# ProPrj_Trumpet_2025-12-14.net
KiCad netlist of a schematic drawn in EasyEDA Pro
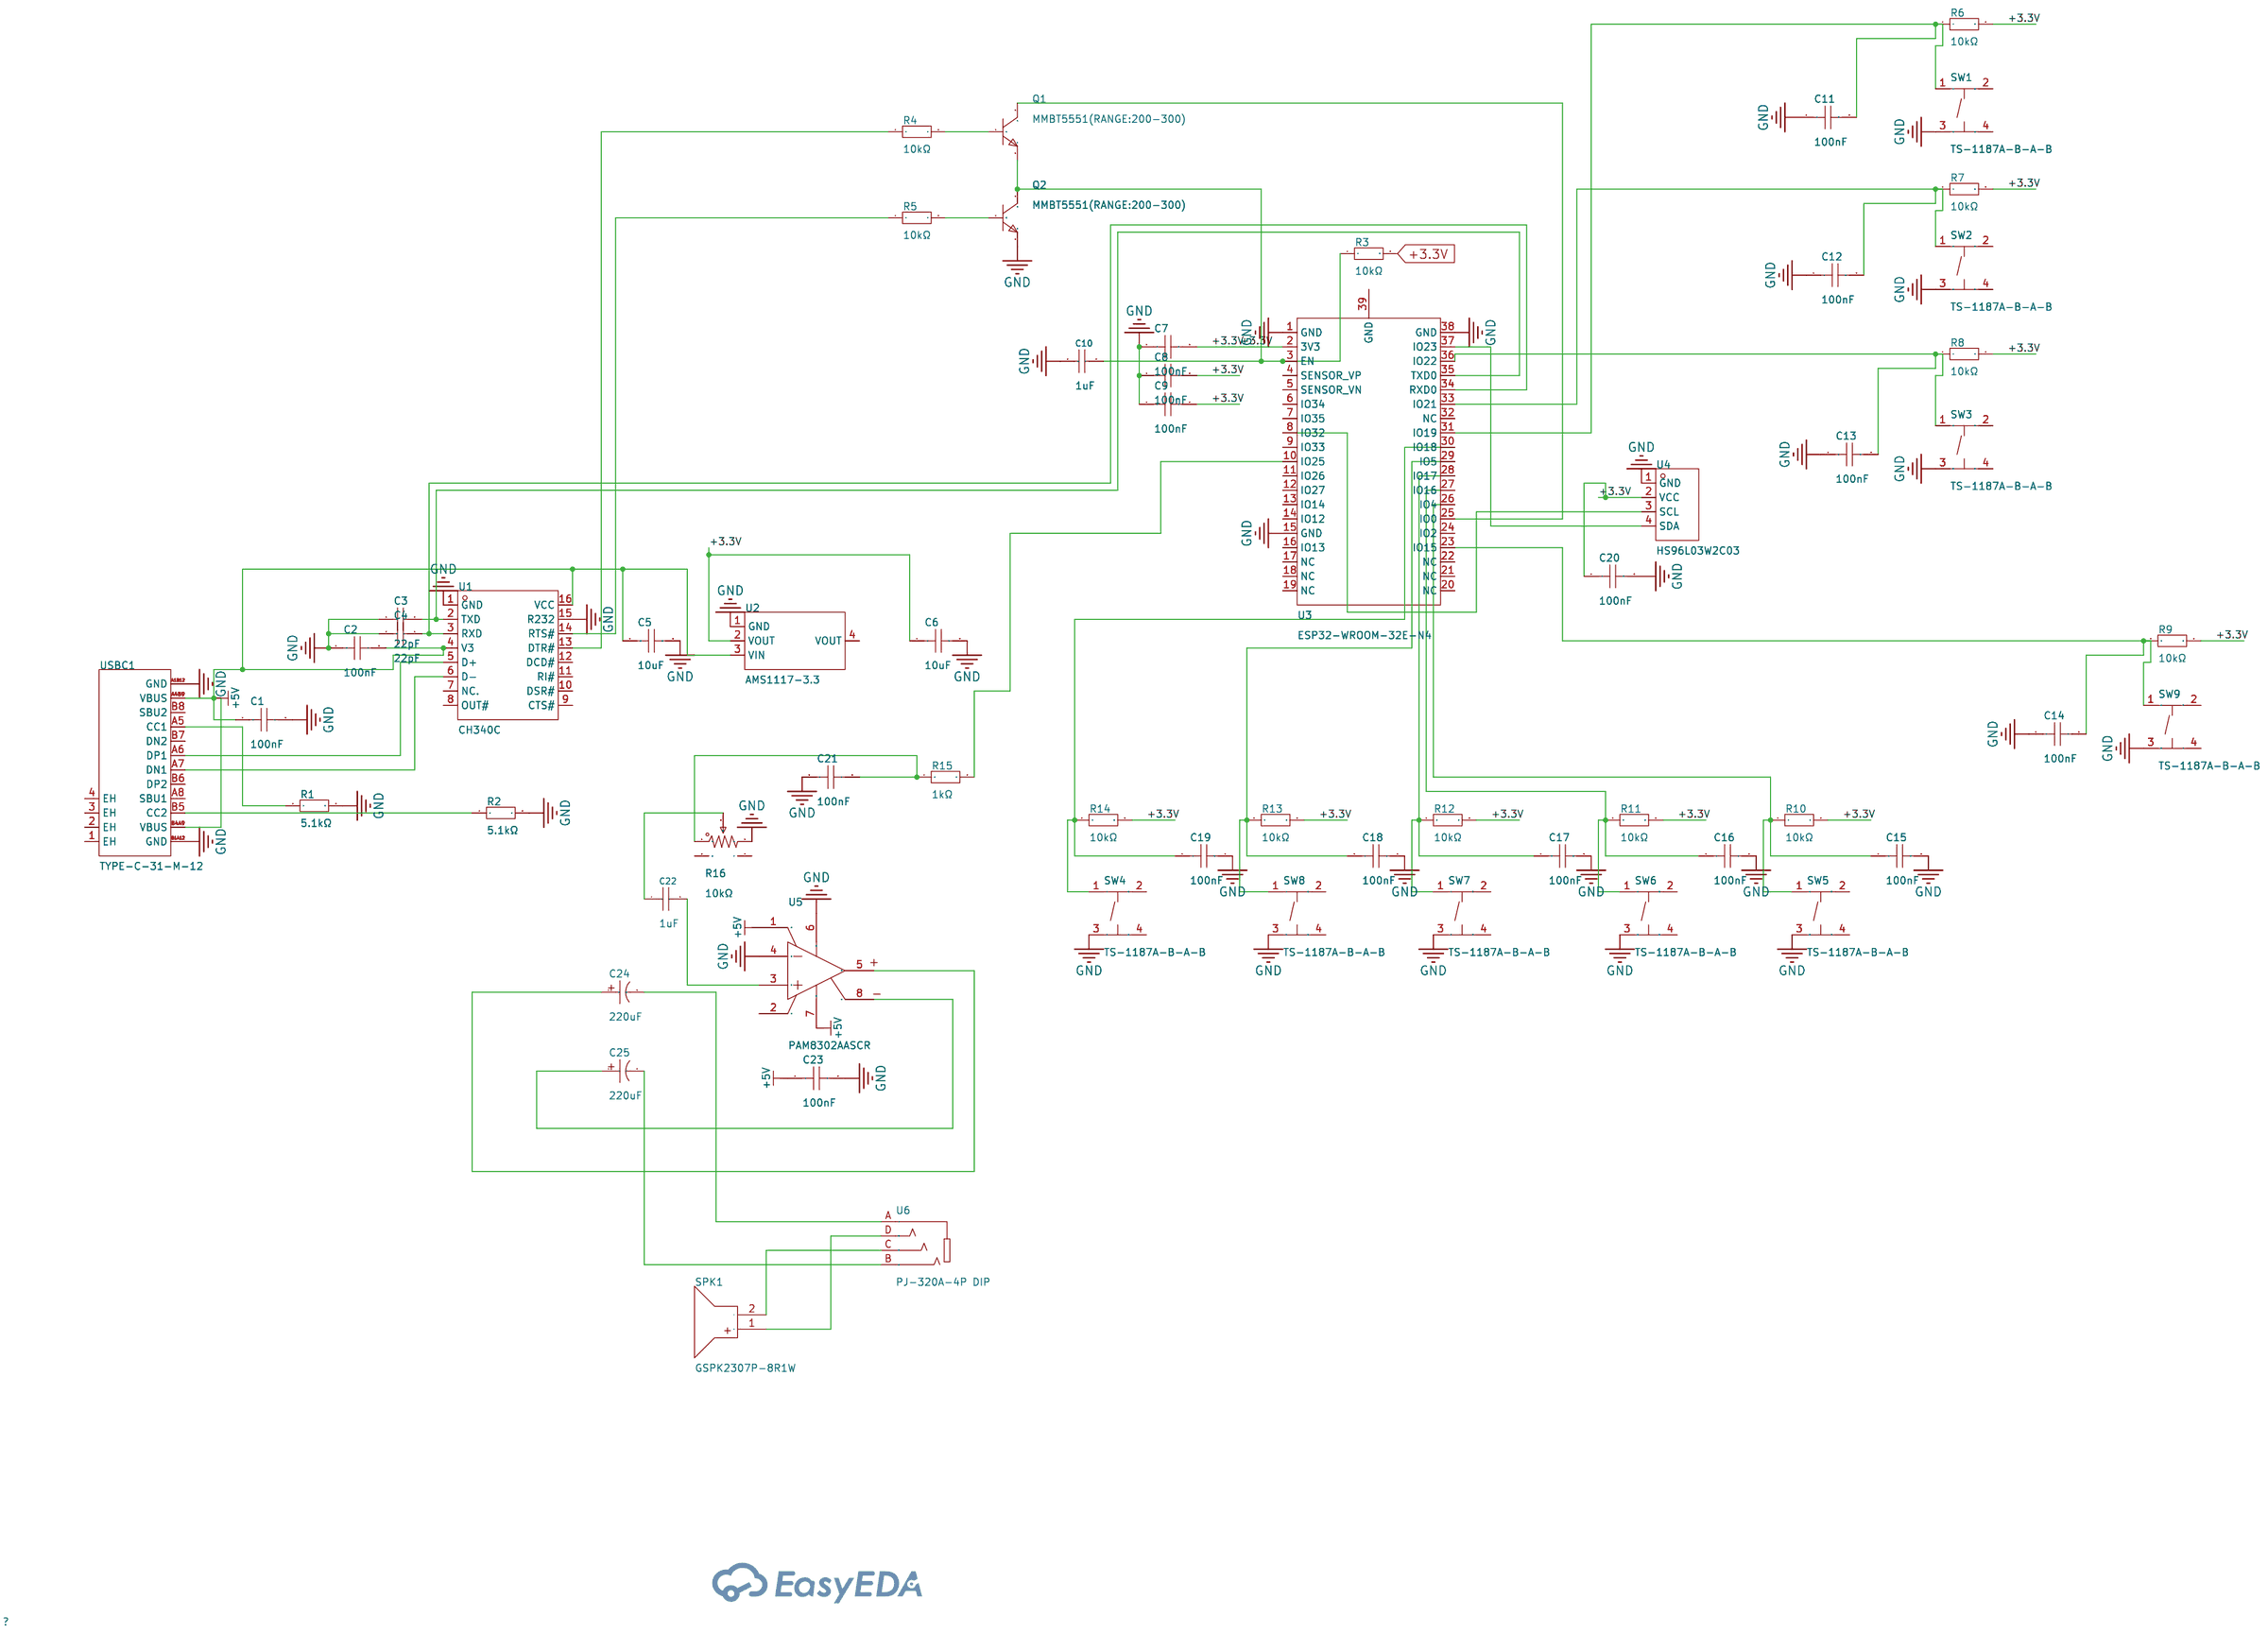
[diagram p0: schematic sheet]

(export (version "E")
  (design (tool "Eeschema 10.0.6"))
  (components
    (comp (ref "C1")
      (value "100nF")
      (footprint "easyedapro:C0805")
      (description "Capacitance:100nF Tolerance:±10% Tolerance:±10% Voltage Rating:50V Temperature Coefficient:X7R")
      (fields
        (field (name "Manufacturer Part") "CC0805KRX7R9BB104")
        (field (name "Manufacturer") "YAGEO(国巨)")
      )
      (libsource (lib "easyedapro") (part "CC0805KRX7R9BB104"))
    )
    (comp (ref "C2")
      (value "100nF")
      (footprint "easyedapro:C0805")
      (description "Capacitance:100nF Tolerance:±10% Tolerance:±10% Voltage Rating:50V Temperature Coefficient:X7R")
      (fields
        (field (name "Manufacturer Part") "CC0805KRX7R9BB104")
        (field (name "Manufacturer") "YAGEO(国巨)")
      )
      (libsource (lib "easyedapro") (part "CC0805KRX7R9BB104"))
    )
    (comp (ref "C3")
      (value "22pF")
      (footprint "easyedapro:C0402")
      (fields (field (name "Manufacturer Part") "0402CG220J500NT") (field (name "Manufacturer") "FH(风华)"))
      (libsource (lib "easyedapro") (part "0402CG220J500NT"))
    )
    (comp (ref "C4")
      (value "22pF")
      (footprint "easyedapro:C0402")
      (fields (field (name "Manufacturer Part") "0402CG220J500NT") (field (name "Manufacturer") "FH(风华)"))
      (libsource (lib "easyedapro") (part "0402CG220J500NT"))
    )
    (comp (ref "C5")
      (value "10uF")
      (footprint "easyedapro:C0805")
      (description "Capacitance:10uF Tolerance:±10% Tolerance:±10% Voltage Rating:25V Temperature Coefficient:X5R")
      (fields
        (field (name "Manufacturer Part") "CL21A106KAYNNNE")
        (field (name "Manufacturer") "SAMSUNG(三星)")
      )
      (libsource (lib "easyedapro") (part "CL21A106KAYNNNE"))
    )
    (comp (ref "C6")
      (value "10uF")
      (footprint "easyedapro:C0805")
      (description "Capacitance:10uF Tolerance:±10% Tolerance:±10% Voltage Rating:25V Temperature Coefficient:X5R")
      (fields
        (field (name "Manufacturer Part") "CL21A106KAYNNNE")
        (field (name "Manufacturer") "SAMSUNG(三星)")
      )
      (libsource (lib "easyedapro") (part "CL21A106KAYNNNE"))
    )
    (comp (ref "C7")
      (value "100nF")
      (footprint "easyedapro:C0805")
      (description "Capacitance:100nF Tolerance:±10% Tolerance:±10% Voltage Rating:50V Temperature Coefficient:X7R")
      (fields
        (field (name "Manufacturer Part") "CC0805KRX7R9BB104")
        (field (name "Manufacturer") "YAGEO(国巨)")
      )
      (libsource (lib "easyedapro") (part "CC0805KRX7R9BB104"))
    )
    (comp (ref "C8")
      (value "100nF")
      (footprint "easyedapro:C0805")
      (description "Capacitance:100nF Tolerance:±10% Tolerance:±10% Voltage Rating:50V Temperature Coefficient:X7R")
      (fields
        (field (name "Manufacturer Part") "CC0805KRX7R9BB104")
        (field (name "Manufacturer") "YAGEO(国巨)")
      )
      (libsource (lib "easyedapro") (part "CC0805KRX7R9BB104"))
    )
    (comp (ref "C9")
      (value "100nF")
      (footprint "easyedapro:C0805")
      (description "Capacitance:100nF Tolerance:±10% Tolerance:±10% Voltage Rating:50V Temperature Coefficient:X7R")
      (fields
        (field (name "Manufacturer Part") "CC0805KRX7R9BB104")
        (field (name "Manufacturer") "YAGEO(国巨)")
      )
      (libsource (lib "easyedapro") (part "CC0805KRX7R9BB104"))
    )
    (comp (ref "C10")
      (value "1uF")
      (footprint "easyedapro:C0805")
      (description "Capacitance:1uF Tolerance:±10% Tolerance:±10% Voltage Rating:50V Temperature Coefficient:X7R")
      (fields
        (field (name "Manufacturer Part") "CL21B105KBFNNNE")
        (field (name "Manufacturer") "SAMSUNG(三星)")
      )
      (libsource (lib "easyedapro") (part "CL21B105KBFNNNE"))
    )
    (comp (ref "C11")
      (value "100nF")
      (footprint "easyedapro:C0805")
      (description "Capacitance:100nF Tolerance:±10% Tolerance:±10% Voltage Rating:50V Temperature Coefficient:X7R")
      (fields
        (field (name "Manufacturer Part") "CC0805KRX7R9BB104")
        (field (name "Manufacturer") "YAGEO(国巨)")
      )
      (libsource (lib "easyedapro") (part "CC0805KRX7R9BB104"))
    )
    (comp (ref "C12")
      (value "100nF")
      (footprint "easyedapro:C0805")
      (description "Capacitance:100nF Tolerance:±10% Tolerance:±10% Voltage Rating:50V Temperature Coefficient:X7R")
      (fields
        (field (name "Manufacturer Part") "CC0805KRX7R9BB104")
        (field (name "Manufacturer") "YAGEO(国巨)")
      )
      (libsource (lib "easyedapro") (part "CC0805KRX7R9BB104"))
    )
    (comp (ref "C13")
      (value "100nF")
      (footprint "easyedapro:C0805")
      (description "Capacitance:100nF Tolerance:±10% Tolerance:±10% Voltage Rating:50V Temperature Coefficient:X7R")
      (fields
        (field (name "Manufacturer Part") "CC0805KRX7R9BB104")
        (field (name "Manufacturer") "YAGEO(国巨)")
      )
      (libsource (lib "easyedapro") (part "CC0805KRX7R9BB104"))
    )
    (comp (ref "C14")
      (value "100nF")
      (footprint "easyedapro:C0805")
      (description "Capacitance:100nF Tolerance:±10% Tolerance:±10% Voltage Rating:50V Temperature Coefficient:X7R")
      (fields
        (field (name "Manufacturer Part") "CC0805KRX7R9BB104")
        (field (name "Manufacturer") "YAGEO(国巨)")
      )
      (libsource (lib "easyedapro") (part "CC0805KRX7R9BB104"))
    )
    (comp (ref "C15")
      (value "100nF")
      (footprint "easyedapro:C0805")
      (description "Capacitance:100nF Tolerance:±10% Tolerance:±10% Voltage Rating:50V Temperature Coefficient:X7R")
      (fields
        (field (name "Manufacturer Part") "CC0805KRX7R9BB104")
        (field (name "Manufacturer") "YAGEO(国巨)")
      )
      (libsource (lib "easyedapro") (part "CC0805KRX7R9BB104"))
    )
    (comp (ref "C16")
      (value "100nF")
      (footprint "easyedapro:C0805")
      (description "Capacitance:100nF Tolerance:±10% Tolerance:±10% Voltage Rating:50V Temperature Coefficient:X7R")
      (fields
        (field (name "Manufacturer Part") "CC0805KRX7R9BB104")
        (field (name "Manufacturer") "YAGEO(国巨)")
      )
      (libsource (lib "easyedapro") (part "CC0805KRX7R9BB104"))
    )
    (comp (ref "C17")
      (value "100nF")
      (footprint "easyedapro:C0805")
      (description "Capacitance:100nF Tolerance:±10% Tolerance:±10% Voltage Rating:50V Temperature Coefficient:X7R")
      (fields
        (field (name "Manufacturer Part") "CC0805KRX7R9BB104")
        (field (name "Manufacturer") "YAGEO(国巨)")
      )
      (libsource (lib "easyedapro") (part "CC0805KRX7R9BB104"))
    )
    (comp (ref "C18")
      (value "100nF")
      (footprint "easyedapro:C0805")
      (description "Capacitance:100nF Tolerance:±10% Tolerance:±10% Voltage Rating:50V Temperature Coefficient:X7R")
      (fields
        (field (name "Manufacturer Part") "CC0805KRX7R9BB104")
        (field (name "Manufacturer") "YAGEO(国巨)")
      )
      (libsource (lib "easyedapro") (part "CC0805KRX7R9BB104"))
    )
    (comp (ref "C19")
      (value "100nF")
      (footprint "easyedapro:C0805")
      (description "Capacitance:100nF Tolerance:±10% Tolerance:±10% Voltage Rating:50V Temperature Coefficient:X7R")
      (fields
        (field (name "Manufacturer Part") "CC0805KRX7R9BB104")
        (field (name "Manufacturer") "YAGEO(国巨)")
      )
      (libsource (lib "easyedapro") (part "CC0805KRX7R9BB104"))
    )
    (comp (ref "C20")
      (value "100nF")
      (footprint "easyedapro:C0805")
      (description "Capacitance:100nF Tolerance:±10% Tolerance:±10% Voltage Rating:50V Temperature Coefficient:X7R")
      (fields
        (field (name "Manufacturer Part") "CC0805KRX7R9BB104")
        (field (name "Manufacturer") "YAGEO(国巨)")
      )
      (libsource (lib "easyedapro") (part "CC0805KRX7R9BB104"))
    )
    (comp (ref "C21")
      (value "100nF")
      (footprint "easyedapro:C0805")
      (description "Capacitance:100nF Tolerance:±10% Tolerance:±10% Voltage Rating:50V Temperature Coefficient:X7R")
      (fields
        (field (name "Manufacturer Part") "CC0805KRX7R9BB104")
        (field (name "Manufacturer") "YAGEO(国巨)")
      )
      (libsource (lib "easyedapro") (part "CC0805KRX7R9BB104"))
    )
    (comp (ref "C22")
      (value "1uF")
      (footprint "easyedapro:C0805")
      (description "Capacitance:1uF Tolerance:±10% Tolerance:±10% Voltage Rating:50V Temperature Coefficient:X7R")
      (fields
        (field (name "Manufacturer Part") "CL21B105KBFNNNE")
        (field (name "Manufacturer") "SAMSUNG(三星)")
      )
      (libsource (lib "easyedapro") (part "CL21B105KBFNNNE"))
    )
    (comp (ref "C23")
      (value "100nF")
      (footprint "easyedapro:C0805")
      (description "Capacitance:100nF Tolerance:±10% Tolerance:±10% Voltage Rating:50V Temperature Coefficient:X7R")
      (fields
        (field (name "Manufacturer Part") "CC0805KRX7R9BB104")
        (field (name "Manufacturer") "YAGEO(国巨)")
      )
      (libsource (lib "easyedapro") (part "CC0805KRX7R9BB104"))
    )
    (comp (ref "C24")
      (value "220uF")
      (footprint "easyedapro:CAP-TH_BD6.3-P2.50-D1.0-FD")
      (fields
        (field (name "Manufacturer Part") "KM227M016E11RR0VH2FP0")
        (field (name "Manufacturer") "Chengx(承兴)")
      )
      (libsource (lib "easyedapro") (part "220uF 16V 6.3*11"))
    )
    (comp (ref "C25")
      (value "220uF")
      (footprint "easyedapro:CAP-TH_BD6.3-P2.50-D1.0-FD")
      (fields
        (field (name "Manufacturer Part") "KM227M016E11RR0VH2FP0")
        (field (name "Manufacturer") "Chengx(承兴)")
      )
      (libsource (lib "easyedapro") (part "220uF 16V 6.3*11"))
    )
    (comp (ref "Q1")
      (value "MMBT5551(RANGE:200-300)")
      (footprint "easyedapro:SOT-23-3_L2.9-W1.3-P1.90-LS2.4-BR")
      (fields (field (name "Manufacturer") "CJ(江苏长电/长晶)"))
      (libsource (lib "easyedapro") (part "MMBT5551_C2145"))
    )
    (comp (ref "Q2")
      (value "MMBT5551(RANGE:200-300)")
      (footprint "easyedapro:SOT-23-3_L2.9-W1.3-P1.90-LS2.4-BR")
      (fields (field (name "Manufacturer") "CJ(江苏长电/长晶)"))
      (libsource (lib "easyedapro") (part "MMBT5551_C2145"))
    )
    (comp (ref "R1")
      (value "5.1kΩ")
      (footprint "easyedapro:R0805")
      (fields
        (field (name "Manufacturer Part") "0805W8F5101T5E")
        (field (name "Manufacturer") "UNI-ROYAL(厚声)")
      )
      (libsource (lib "easyedapro") (part "0805W8F5101T5E"))
    )
    (comp (ref "R2")
      (value "5.1kΩ")
      (footprint "easyedapro:R0805")
      (fields
        (field (name "Manufacturer Part") "0805W8F5101T5E")
        (field (name "Manufacturer") "UNI-ROYAL(厚声)")
      )
      (libsource (lib "easyedapro") (part "0805W8F5101T5E"))
    )
    (comp (ref "R3")
      (value "10kΩ")
      (footprint "easyedapro:R0805")
      (fields
        (field (name "Manufacturer Part") "0805W8F1002T5E")
        (field (name "Manufacturer") "UNI-ROYAL(厚声)")
      )
      (libsource (lib "easyedapro") (part "0805W8F1002T5E"))
    )
    (comp (ref "R4")
      (value "10kΩ")
      (footprint "easyedapro:R0805")
      (fields
        (field (name "Manufacturer Part") "0805W8F1002T5E")
        (field (name "Manufacturer") "UNI-ROYAL(厚声)")
      )
      (libsource (lib "easyedapro") (part "0805W8F1002T5E"))
    )
    (comp (ref "R5")
      (value "10kΩ")
      (footprint "easyedapro:R0805")
      (fields
        (field (name "Manufacturer Part") "0805W8F1002T5E")
        (field (name "Manufacturer") "UNI-ROYAL(厚声)")
      )
      (libsource (lib "easyedapro") (part "0805W8F1002T5E"))
    )
    (comp (ref "R6")
      (value "10kΩ")
      (footprint "easyedapro:R0805")
      (fields
        (field (name "Manufacturer Part") "0805W8F1002T5E")
        (field (name "Manufacturer") "UNI-ROYAL(厚声)")
      )
      (libsource (lib "easyedapro") (part "0805W8F1002T5E"))
    )
    (comp (ref "R7")
      (value "10kΩ")
      (footprint "easyedapro:R0805")
      (fields
        (field (name "Manufacturer Part") "0805W8F1002T5E")
        (field (name "Manufacturer") "UNI-ROYAL(厚声)")
      )
      (libsource (lib "easyedapro") (part "0805W8F1002T5E"))
    )
    (comp (ref "R8")
      (value "10kΩ")
      (footprint "easyedapro:R0805")
      (fields
        (field (name "Manufacturer Part") "0805W8F1002T5E")
        (field (name "Manufacturer") "UNI-ROYAL(厚声)")
      )
      (libsource (lib "easyedapro") (part "0805W8F1002T5E"))
    )
    (comp (ref "R9")
      (value "10kΩ")
      (footprint "easyedapro:R0805")
      (fields
        (field (name "Manufacturer Part") "0805W8F1002T5E")
        (field (name "Manufacturer") "UNI-ROYAL(厚声)")
      )
      (libsource (lib "easyedapro") (part "0805W8F1002T5E"))
    )
    (comp (ref "R10")
      (value "10kΩ")
      (footprint "easyedapro:R0805")
      (fields
        (field (name "Manufacturer Part") "0805W8F1002T5E")
        (field (name "Manufacturer") "UNI-ROYAL(厚声)")
      )
      (libsource (lib "easyedapro") (part "0805W8F1002T5E"))
    )
    (comp (ref "R11")
      (value "10kΩ")
      (footprint "easyedapro:R0805")
      (fields
        (field (name "Manufacturer Part") "0805W8F1002T5E")
        (field (name "Manufacturer") "UNI-ROYAL(厚声)")
      )
      (libsource (lib "easyedapro") (part "0805W8F1002T5E"))
    )
    (comp (ref "R12")
      (value "10kΩ")
      (footprint "easyedapro:R0805")
      (fields
        (field (name "Manufacturer Part") "0805W8F1002T5E")
        (field (name "Manufacturer") "UNI-ROYAL(厚声)")
      )
      (libsource (lib "easyedapro") (part "0805W8F1002T5E"))
    )
    (comp (ref "R13")
      (value "10kΩ")
      (footprint "easyedapro:R0805")
      (fields
        (field (name "Manufacturer Part") "0805W8F1002T5E")
        (field (name "Manufacturer") "UNI-ROYAL(厚声)")
      )
      (libsource (lib "easyedapro") (part "0805W8F1002T5E"))
    )
    (comp (ref "R14")
      (value "10kΩ")
      (footprint "easyedapro:R0805")
      (fields
        (field (name "Manufacturer Part") "0805W8F1002T5E")
        (field (name "Manufacturer") "UNI-ROYAL(厚声)")
      )
      (libsource (lib "easyedapro") (part "0805W8F1002T5E"))
    )
    (comp (ref "R15")
      (value "1kΩ")
      (footprint "easyedapro:R0805")
      (fields
        (field (name "Manufacturer Part") "0805W8F1001T5E")
        (field (name "Manufacturer") "UNI-ROYAL(厚声)")
      )
      (libsource (lib "easyedapro") (part "0805W8F1001T5E"))
    )
    (comp (ref "R16")
      (value "10kΩ")
      (footprint "easyedapro:RES-ADJ-TH_RK09L1140A5P")
      (description "Resistance: Tolerance:±20% Tolerance:±20% Rated Voltage: Power(Watts):50mW Turns:-")
      (fields
        (field (name "Manufacturer Part") "RK09L114001T")
        (field (name "Manufacturer") "ALPSALPINE(阿尔卑斯阿尔派)")
      )
      (libsource (lib "easyedapro") (part "RK09L114001T"))
    )
    (comp (ref "SPK1")
      (value "GSPK2307P-8R1W")
      (footprint "easyedapro:SPK-TH_BD23.0-P10.00-D0.8-L-RD")
      (fields (field (name "Manufacturer") "INGHAi(赢海)"))
      (libsource (lib "easyedapro") (part "GSPK2307P-8R1W"))
    )
    (comp (ref "SW1")
      (value "TS-1187A-B-A-B")
      (footprint "easyedapro:SW-SMD_4P-L5.1-W5.1-P3.70-LS6.5-TL_H1.5")
      (fields (field (name "Manufacturer") "XKB Connection(中国星坤)"))
      (libsource (lib "easyedapro") (part "TS-1187A-B-A-B"))
    )
    (comp (ref "SW2")
      (value "TS-1187A-B-A-B")
      (footprint "easyedapro:SW-SMD_4P-L5.1-W5.1-P3.70-LS6.5-TL_H1.5")
      (fields (field (name "Manufacturer") "XKB Connection(中国星坤)"))
      (libsource (lib "easyedapro") (part "TS-1187A-B-A-B"))
    )
    (comp (ref "SW3")
      (value "TS-1187A-B-A-B")
      (footprint "easyedapro:SW-SMD_4P-L5.1-W5.1-P3.70-LS6.5-TL_H1.5")
      (fields (field (name "Manufacturer") "XKB Connection(中国星坤)"))
      (libsource (lib "easyedapro") (part "TS-1187A-B-A-B"))
    )
    (comp (ref "SW4")
      (value "TS-1187A-B-A-B")
      (footprint "easyedapro:SW-SMD_4P-L5.1-W5.1-P3.70-LS6.5-TL_H1.5")
      (fields (field (name "Manufacturer") "XKB Connection(中国星坤)"))
      (libsource (lib "easyedapro") (part "TS-1187A-B-A-B"))
    )
    (comp (ref "SW5")
      (value "TS-1187A-B-A-B")
      (footprint "easyedapro:SW-SMD_4P-L5.1-W5.1-P3.70-LS6.5-TL_H1.5")
      (fields (field (name "Manufacturer") "XKB Connection(中国星坤)"))
      (libsource (lib "easyedapro") (part "TS-1187A-B-A-B"))
    )
    (comp (ref "SW6")
      (value "TS-1187A-B-A-B")
      (footprint "easyedapro:SW-SMD_4P-L5.1-W5.1-P3.70-LS6.5-TL_H1.5")
      (fields (field (name "Manufacturer") "XKB Connection(中国星坤)"))
      (libsource (lib "easyedapro") (part "TS-1187A-B-A-B"))
    )
    (comp (ref "SW7")
      (value "TS-1187A-B-A-B")
      (footprint "easyedapro:SW-SMD_4P-L5.1-W5.1-P3.70-LS6.5-TL_H1.5")
      (fields (field (name "Manufacturer") "XKB Connection(中国星坤)"))
      (libsource (lib "easyedapro") (part "TS-1187A-B-A-B"))
    )
    (comp (ref "SW8")
      (value "TS-1187A-B-A-B")
      (footprint "easyedapro:SW-SMD_4P-L5.1-W5.1-P3.70-LS6.5-TL_H1.5")
      (fields (field (name "Manufacturer") "XKB Connection(中国星坤)"))
      (libsource (lib "easyedapro") (part "TS-1187A-B-A-B"))
    )
    (comp (ref "SW9")
      (value "TS-1187A-B-A-B")
      (footprint "easyedapro:SW-SMD_4P-L5.1-W5.1-P3.70-LS6.5-TL_H1.5")
      (fields (field (name "Manufacturer") "XKB Connection(中国星坤)"))
      (libsource (lib "easyedapro") (part "TS-1187A-B-A-B"))
    )
    (comp (ref "U1")
      (value "CH340C")
      (footprint "easyedapro:SOP-16_L10.0-W3.9-P1.27-LS6.0-BL")
      (fields (field (name "Manufacturer") "WCH(南京沁恒)"))
      (libsource (lib "easyedapro") (part "CH340C"))
    )
    (comp (ref "U2")
      (value "AMS1117-3.3")
      (footprint "easyedapro:SOT-223-3_L6.5-W3.4-P2.30-LS7.0-BR")
      (fields (field (name "Manufacturer") "AMS"))
      (libsource (lib "easyedapro") (part "AMS1117-3.3"))
    )
    (comp (ref "U3")
      (value "ESP32-WROOM-32E-N4")
      (footprint "easyedapro:WIFI-SMD_ESP32-WROOM-32E")
      (fields (field (name "Manufacturer") "ESPRESSIF(乐鑫)"))
      (libsource (lib "easyedapro") (part "ESP32-WROOM-32E(4MB)"))
    )
    (comp (ref "U4")
      (value "HS96L03W2C03")
      (footprint "easyedapro:OLED-TH_L27.8-W27.2-P2.54_C9900033791")
      (fields (field (name "Manufacturer") "HS(汉昇)"))
      (libsource (lib "easyedapro") (part "HS96L03W2C03"))
    )
    (comp (ref "U5")
      (value "PAM8302AASCR")
      (footprint "easyedapro:MSOP-8_L3.0-W3.0-P0.65-LS5.0-BL")
      (fields (field (name "Manufacturer") "DIODES(美台)"))
      (libsource (lib "easyedapro") (part "PAM8302AASCR"))
    )
    (comp (ref "U6")
      (value "PJ-320A-4P DIP")
      (footprint "easyedapro:AUDIO-TH_PJ-320A-4P-DIP")
      (fields (field (name "Manufacturer") "SHOU HAN(首韩)"))
      (libsource (lib "easyedapro") (part "PJ-320A-4P DIP"))
    )
    (comp (ref "USBC1")
      (value "TYPE-C-31-M-12")
      (footprint "easyedapro:USB-C_SMD-TYPE-C-31-M-12_1")
      (fields (field (name "Manufacturer") "韩国韩荣"))
      (libsource (lib "easyedapro") (part "TYPE-C-31-M-12"))
    )
  )
  (nets
    (net (code "1") (name "+3.3V") (class "Default")
      (node (ref "C20") (pin "1") (pinfunction "1_1") (pintype "unspecified"))
      (node (ref "C6") (pin "1") (pinfunction "1_1") (pintype "unspecified"))
      (node (ref "C7") (pin "2") (pinfunction "2_2") (pintype "unspecified"))
      (node (ref "C8") (pin "2") (pinfunction "2_2") (pintype "unspecified"))
      (node (ref "C9") (pin "2") (pinfunction "2_2") (pintype "unspecified"))
      (node (ref "R10") (pin "2") (pinfunction "2_2") (pintype "input"))
      (node (ref "R11") (pin "2") (pinfunction "2_2") (pintype "input"))
      (node (ref "R12") (pin "2") (pinfunction "2_2") (pintype "input"))
      (node (ref "R13") (pin "2") (pinfunction "2_2") (pintype "input"))
      (node (ref "R14") (pin "2") (pinfunction "2_2") (pintype "input"))
      (node (ref "R3") (pin "2") (pinfunction "2_2") (pintype "input"))
      (node (ref "R6") (pin "2") (pinfunction "2_2") (pintype "input"))
      (node (ref "R7") (pin "2") (pinfunction "2_2") (pintype "input"))
      (node (ref "R8") (pin "2") (pinfunction "2_2") (pintype "input"))
      (node (ref "R9") (pin "2") (pinfunction "2_2") (pintype "input"))
      (node (ref "U2") (pin "2") (pinfunction "VOUT_2") (pintype "unspecified"))
      (node (ref "U3") (pin "2") (pinfunction "3V3_2") (pintype "unspecified"))
      (node (ref "U4") (pin "2") (pinfunction "VCC_2") (pintype "unspecified"))
    )
    (net (code "2") (name "+5V") (class "Default")
      (node (ref "C1") (pin "1") (pinfunction "1_1") (pintype "unspecified"))
      (node (ref "C2") (pin "2") (pinfunction "2_2") (pintype "unspecified"))
      (node (ref "C23") (pin "1") (pinfunction "1_1") (pintype "unspecified"))
      (node (ref "C5") (pin "1") (pinfunction "1_1") (pintype "unspecified"))
      (node (ref "U1") (pin "16") (pinfunction "VCC_16") (pintype "unspecified"))
      (node (ref "U1") (pin "4") (pinfunction "V3_4") (pintype "unspecified"))
      (node (ref "U2") (pin "3") (pinfunction "VIN_3") (pintype "unspecified"))
      (node (ref "U5") (pin "1") (pinfunction "SD#_1") (pintype "unspecified"))
      (node (ref "U5") (pin "7") (pinfunction "GND_7") (pintype "unspecified"))
      (node (ref "USBC1") (pin "A4B9") (pinfunction "VBUS_A4B9") (pintype "unspecified"))
      (node (ref "USBC1") (pin "B4A9") (pinfunction "VBUS_B4A9") (pintype "unspecified"))
    )
    (net (code "3") (name "GND") (class "Default")
      (node (ref "C1") (pin "2") (pinfunction "2_2") (pintype "unspecified"))
      (node (ref "C10") (pin "1") (pinfunction "1_1") (pintype "input"))
      (node (ref "C11") (pin "1") (pinfunction "1_1") (pintype "unspecified"))
      (node (ref "C12") (pin "1") (pinfunction "1_1") (pintype "unspecified"))
      (node (ref "C13") (pin "1") (pinfunction "1_1") (pintype "unspecified"))
      (node (ref "C14") (pin "1") (pinfunction "1_1") (pintype "unspecified"))
      (node (ref "C15") (pin "2") (pinfunction "2_2") (pintype "unspecified"))
      (node (ref "C16") (pin "2") (pinfunction "2_2") (pintype "unspecified"))
      (node (ref "C17") (pin "2") (pinfunction "2_2") (pintype "unspecified"))
      (node (ref "C18") (pin "2") (pinfunction "2_2") (pintype "unspecified"))
      (node (ref "C19") (pin "2") (pinfunction "2_2") (pintype "unspecified"))
      (node (ref "C2") (pin "1") (pinfunction "1_1") (pintype "unspecified"))
      (node (ref "C20") (pin "2") (pinfunction "2_2") (pintype "unspecified"))
      (node (ref "C21") (pin "1") (pinfunction "1_1") (pintype "unspecified"))
      (node (ref "C23") (pin "2") (pinfunction "2_2") (pintype "unspecified"))
      (node (ref "C3") (pin "1") (pinfunction "1_1") (pintype "input"))
      (node (ref "C4") (pin "1") (pinfunction "1_1") (pintype "input"))
      (node (ref "C5") (pin "2") (pinfunction "2_2") (pintype "unspecified"))
      (node (ref "C6") (pin "2") (pinfunction "2_2") (pintype "unspecified"))
      (node (ref "C7") (pin "1") (pinfunction "1_1") (pintype "unspecified"))
      (node (ref "C8") (pin "1") (pinfunction "1_1") (pintype "unspecified"))
      (node (ref "C9") (pin "1") (pinfunction "1_1") (pintype "unspecified"))
      (node (ref "Q2") (pin "2") (pinfunction "E_2") (pintype "unspecified"))
      (node (ref "R1") (pin "2") (pinfunction "2_2") (pintype "input"))
      (node (ref "R16") (pin "3") (pinfunction "3_3") (pintype "unspecified"))
      (node (ref "R2") (pin "2") (pinfunction "2_2") (pintype "input"))
      (node (ref "SW1") (pin "3") (pinfunction "C_3") (pintype "unspecified"))
      (node (ref "SW2") (pin "3") (pinfunction "C_3") (pintype "unspecified"))
      (node (ref "SW3") (pin "3") (pinfunction "C_3") (pintype "unspecified"))
      (node (ref "SW4") (pin "3") (pinfunction "C_3") (pintype "unspecified"))
      (node (ref "SW5") (pin "3") (pinfunction "C_3") (pintype "unspecified"))
      (node (ref "SW6") (pin "3") (pinfunction "C_3") (pintype "unspecified"))
      (node (ref "SW7") (pin "3") (pinfunction "C_3") (pintype "unspecified"))
      (node (ref "SW8") (pin "3") (pinfunction "C_3") (pintype "unspecified"))
      (node (ref "SW9") (pin "3") (pinfunction "C_3") (pintype "unspecified"))
      (node (ref "U1") (pin "1") (pinfunction "GND_1") (pintype "unspecified"))
      (node (ref "U1") (pin "15") (pinfunction "R232_15") (pintype "unspecified"))
      (node (ref "U2") (pin "1") (pinfunction "GND_1") (pintype "unspecified"))
      (node (ref "U3") (pin "1") (pinfunction "GND_1") (pintype "unspecified"))
      (node (ref "U3") (pin "15") (pinfunction "GND_15") (pintype "unspecified"))
      (node (ref "U3") (pin "38") (pinfunction "GND_38") (pintype "unspecified"))
      (node (ref "U4") (pin "1") (pinfunction "GND_1") (pintype "unspecified"))
      (node (ref "U5") (pin "4") (pinfunction "IN-_4") (pintype "unspecified"))
      (node (ref "U5") (pin "6") (pinfunction "VDD_6") (pintype "unspecified"))
      (node (ref "USBC1") (pin "A1B12") (pinfunction "GND_A1B12") (pintype "unspecified"))
      (node (ref "USBC1") (pin "B1A12") (pinfunction "GND_B1A12") (pintype "unspecified"))
    )
    (net (code "4") (name "Net-(C21-Pad2)") (class "Default")
      (node (ref "C21") (pin "2") (pinfunction "2_2") (pintype "unspecified"))
      (node (ref "R15") (pin "1") (pinfunction "1_1") (pintype "input"))
      (node (ref "R16") (pin "1") (pinfunction "1_1") (pintype "unspecified"))
    )
    (net (code "5") (name "Net-(C22-Pad1)") (class "Default")
      (node (ref "C22") (pin "1") (pinfunction "1_1") (pintype "input"))
      (node (ref "R16") (pin "2") (pinfunction "2_2") (pintype "unspecified"))
    )
    (net (code "6") (name "Net-(C24-Pad2)") (class "Default")
      (node (ref "C24") (pin "2") (pinfunction "2_2") (pintype "input"))
      (node (ref "U6") (pin "A") (pinfunction "A_A") (pintype "unspecified"))
    )
    (net (code "7") (name "Net-(C25-Pad2)") (class "Default")
      (node (ref "C25") (pin "2") (pinfunction "2_2") (pintype "input"))
      (node (ref "U6") (pin "B") (pinfunction "B_B") (pintype "unspecified"))
    )
    (net (code "8") (name "Net-(Q1-B)") (class "Default")
      (node (ref "Q1") (pin "1") (pinfunction "B_1") (pintype "unspecified"))
      (node (ref "R4") (pin "2") (pinfunction "2_2") (pintype "input"))
    )
    (net (code "9") (name "Net-(Q1-C)") (class "Default")
      (node (ref "Q1") (pin "3") (pinfunction "C_3") (pintype "unspecified"))
      (node (ref "U3") (pin "25") (pinfunction "IO0_25") (pintype "unspecified"))
    )
    (net (code "10") (name "Net-(Q1-E)") (class "Default")
      (node (ref "C10") (pin "2") (pinfunction "2_2") (pintype "input"))
      (node (ref "Q1") (pin "2") (pinfunction "E_2") (pintype "unspecified"))
      (node (ref "Q2") (pin "3") (pinfunction "C_3") (pintype "unspecified"))
      (node (ref "R3") (pin "1") (pinfunction "1_1") (pintype "input"))
      (node (ref "U3") (pin "3") (pinfunction "EN_3") (pintype "unspecified"))
    )
    (net (code "11") (name "Net-(Q2-B)") (class "Default")
      (node (ref "Q2") (pin "1") (pinfunction "B_1") (pintype "unspecified"))
      (node (ref "R5") (pin "2") (pinfunction "2_2") (pintype "input"))
    )
    (net (code "12") (name "Net-(SPK1-+)") (class "Default")
      (node (ref "SPK1") (pin "1") (pinfunction "+_1") (pintype "unspecified"))
      (node (ref "U6") (pin "D") (pinfunction "D_D") (pintype "unspecified"))
    )
    (net (code "13") (name "Net-(SPK1--)") (class "Default")
      (node (ref "SPK1") (pin "2") (pinfunction "-_2") (pintype "unspecified"))
      (node (ref "U6") (pin "C") (pinfunction "C_C") (pintype "unspecified"))
    )
    (net (code "14") (name "Net-(SW1-A)") (class "Default")
      (node (ref "C11") (pin "2") (pinfunction "2_2") (pintype "unspecified"))
      (node (ref "R6") (pin "1") (pinfunction "1_1") (pintype "input"))
      (node (ref "SW1") (pin "1") (pinfunction "A_1") (pintype "unspecified"))
      (node (ref "U3") (pin "31") (pinfunction "IO19_31") (pintype "unspecified"))
    )
    (net (code "15") (name "Net-(SW2-A)") (class "Default")
      (node (ref "C12") (pin "2") (pinfunction "2_2") (pintype "unspecified"))
      (node (ref "R7") (pin "1") (pinfunction "1_1") (pintype "input"))
      (node (ref "SW2") (pin "1") (pinfunction "A_1") (pintype "unspecified"))
      (node (ref "U3") (pin "33") (pinfunction "IO21_33") (pintype "unspecified"))
    )
    (net (code "16") (name "Net-(SW3-A)") (class "Default")
      (node (ref "C13") (pin "2") (pinfunction "2_2") (pintype "unspecified"))
      (node (ref "R8") (pin "1") (pinfunction "1_1") (pintype "input"))
      (node (ref "SW3") (pin "1") (pinfunction "A_1") (pintype "unspecified"))
      (node (ref "U3") (pin "36") (pinfunction "IO22_36") (pintype "unspecified"))
    )
    (net (code "17") (name "Net-(SW4-A)") (class "Default")
      (node (ref "C19") (pin "1") (pinfunction "1_1") (pintype "unspecified"))
      (node (ref "R14") (pin "1") (pinfunction "1_1") (pintype "input"))
      (node (ref "SW4") (pin "1") (pinfunction "A_1") (pintype "unspecified"))
      (node (ref "U3") (pin "30") (pinfunction "IO18_30") (pintype "unspecified"))
    )
    (net (code "18") (name "Net-(SW5-A)") (class "Default")
      (node (ref "C15") (pin "1") (pinfunction "1_1") (pintype "unspecified"))
      (node (ref "R10") (pin "1") (pinfunction "1_1") (pintype "input"))
      (node (ref "SW5") (pin "1") (pinfunction "A_1") (pintype "unspecified"))
      (node (ref "U3") (pin "26") (pinfunction "IO4_26") (pintype "unspecified"))
    )
    (net (code "19") (name "Net-(SW6-A)") (class "Default")
      (node (ref "C16") (pin "1") (pinfunction "1_1") (pintype "unspecified"))
      (node (ref "R11") (pin "1") (pinfunction "1_1") (pintype "input"))
      (node (ref "SW6") (pin "1") (pinfunction "A_1") (pintype "unspecified"))
      (node (ref "U3") (pin "27") (pinfunction "IO16_27") (pintype "unspecified"))
    )
    (net (code "20") (name "Net-(SW7-A)") (class "Default")
      (node (ref "C17") (pin "1") (pinfunction "1_1") (pintype "unspecified"))
      (node (ref "R12") (pin "1") (pinfunction "1_1") (pintype "input"))
      (node (ref "SW7") (pin "1") (pinfunction "A_1") (pintype "unspecified"))
      (node (ref "U3") (pin "28") (pinfunction "IO17_28") (pintype "unspecified"))
    )
    (net (code "21") (name "Net-(SW8-A)") (class "Default")
      (node (ref "C18") (pin "1") (pinfunction "1_1") (pintype "unspecified"))
      (node (ref "R13") (pin "1") (pinfunction "1_1") (pintype "input"))
      (node (ref "SW8") (pin "1") (pinfunction "A_1") (pintype "unspecified"))
      (node (ref "U3") (pin "29") (pinfunction "IO5_29") (pintype "unspecified"))
    )
    (net (code "22") (name "Net-(SW9-A)") (class "Default")
      (node (ref "C14") (pin "2") (pinfunction "2_2") (pintype "unspecified"))
      (node (ref "R9") (pin "1") (pinfunction "1_1") (pintype "input"))
      (node (ref "SW9") (pin "1") (pinfunction "A_1") (pintype "unspecified"))
      (node (ref "U3") (pin "23") (pinfunction "IO15_23") (pintype "unspecified"))
    )
    (net (code "23") (name "Net-(U1-D+)") (class "Default")
      (node (ref "U1") (pin "5") (pinfunction "D+_5") (pintype "unspecified"))
      (node (ref "USBC1") (pin "A6") (pinfunction "DP1_A6") (pintype "unspecified"))
    )
    (net (code "24") (name "Net-(U1-D-)") (class "Default")
      (node (ref "U1") (pin "6") (pinfunction "D-_6") (pintype "unspecified"))
      (node (ref "USBC1") (pin "A7") (pinfunction "DN1_A7") (pintype "unspecified"))
    )
    (net (code "25") (name "Net-(U1-DTR#)") (class "Default")
      (node (ref "R4") (pin "1") (pinfunction "1_1") (pintype "input"))
      (node (ref "U1") (pin "13") (pinfunction "DTR#_13") (pintype "unspecified"))
    )
    (net (code "26") (name "Net-(U1-RTS#)") (class "Default")
      (node (ref "R5") (pin "1") (pinfunction "1_1") (pintype "input"))
      (node (ref "U1") (pin "14") (pinfunction "RTS#_14") (pintype "unspecified"))
    )
    (net (code "27") (name "Net-(U1-RXD)") (class "Default")
      (node (ref "C4") (pin "2") (pinfunction "2_2") (pintype "input"))
      (node (ref "U1") (pin "3") (pinfunction "RXD_3") (pintype "unspecified"))
      (node (ref "U3") (pin "34") (pinfunction "RXD0_34") (pintype "unspecified"))
    )
    (net (code "28") (name "Net-(U1-TXD)") (class "Default")
      (node (ref "C3") (pin "2") (pinfunction "2_2") (pintype "input"))
      (node (ref "U1") (pin "2") (pinfunction "TXD_2") (pintype "unspecified"))
      (node (ref "U3") (pin "35") (pinfunction "TXD0_35") (pintype "unspecified"))
    )
    (net (code "29") (name "Net-(U3-IO23)") (class "Default")
      (node (ref "U3") (pin "37") (pinfunction "IO23_37") (pintype "unspecified"))
      (node (ref "U4") (pin "4") (pinfunction "SDA_4") (pintype "unspecified"))
    )
    (net (code "30") (name "Net-(U3-IO25)") (class "Default")
      (node (ref "R15") (pin "2") (pinfunction "2_2") (pintype "input"))
      (node (ref "U3") (pin "10") (pinfunction "IO25_10") (pintype "unspecified"))
    )
    (net (code "31") (name "Net-(U3-IO32)") (class "Default")
      (node (ref "U3") (pin "8") (pinfunction "IO32_8") (pintype "unspecified"))
      (node (ref "U4") (pin "3") (pinfunction "SCL_3") (pintype "unspecified"))
    )
    (net (code "32") (name "Net-(U5-IN+)") (class "Default")
      (node (ref "C22") (pin "2") (pinfunction "2_2") (pintype "input"))
      (node (ref "U5") (pin "3") (pinfunction "IN+_3") (pintype "unspecified"))
    )
    (net (code "33") (name "Net-(U5-VO+)") (class "Default")
      (node (ref "C24") (pin "1") (pinfunction "1_1") (pintype "input"))
      (node (ref "U5") (pin "5") (pinfunction "VO+_5") (pintype "output"))
    )
    (net (code "34") (name "Net-(U5-VO-)") (class "Default")
      (node (ref "C25") (pin "1") (pinfunction "1_1") (pintype "input"))
      (node (ref "U5") (pin "8") (pinfunction "VO-_8") (pintype "unspecified"))
    )
    (net (code "35") (name "Net-(USBC1-CC1)") (class "Default")
      (node (ref "R1") (pin "1") (pinfunction "1_1") (pintype "input"))
      (node (ref "USBC1") (pin "A5") (pinfunction "CC1_A5") (pintype "unspecified"))
    )
    (net (code "36") (name "Net-(USBC1-CC2)") (class "Default")
      (node (ref "R2") (pin "1") (pinfunction "1_1") (pintype "input"))
      (node (ref "USBC1") (pin "B5") (pinfunction "CC2_B5") (pintype "unspecified"))
    )
    (net (code "37") (name "unconnected-(R16-Pad4)") (class "Default")
      (node (ref "R16") (pin "4") (pinfunction "4_4") (pintype "unspecified"))
    )
    (net (code "38") (name "unconnected-(R16-Pad5)") (class "Default")
      (node (ref "R16") (pin "5") (pinfunction "5_5") (pintype "unspecified"))
    )
    (net (code "39") (name "unconnected-(SW1-B-Pad2)") (class "Default")
      (node (ref "SW1") (pin "2") (pinfunction "B_2") (pintype "unspecified"))
    )
    (net (code "40") (name "unconnected-(SW1-D-Pad4)") (class "Default")
      (node (ref "SW1") (pin "4") (pinfunction "D_4") (pintype "unspecified"))
    )
    (net (code "41") (name "unconnected-(SW2-B-Pad2)") (class "Default")
      (node (ref "SW2") (pin "2") (pinfunction "B_2") (pintype "unspecified"))
    )
    (net (code "42") (name "unconnected-(SW2-D-Pad4)") (class "Default")
      (node (ref "SW2") (pin "4") (pinfunction "D_4") (pintype "unspecified"))
    )
    (net (code "43") (name "unconnected-(SW3-B-Pad2)") (class "Default")
      (node (ref "SW3") (pin "2") (pinfunction "B_2") (pintype "unspecified"))
    )
    (net (code "44") (name "unconnected-(SW3-D-Pad4)") (class "Default")
      (node (ref "SW3") (pin "4") (pinfunction "D_4") (pintype "unspecified"))
    )
    (net (code "45") (name "unconnected-(SW4-B-Pad2)") (class "Default")
      (node (ref "SW4") (pin "2") (pinfunction "B_2") (pintype "unspecified"))
    )
    (net (code "46") (name "unconnected-(SW4-D-Pad4)") (class "Default")
      (node (ref "SW4") (pin "4") (pinfunction "D_4") (pintype "unspecified"))
    )
    (net (code "47") (name "unconnected-(SW5-B-Pad2)") (class "Default")
      (node (ref "SW5") (pin "2") (pinfunction "B_2") (pintype "unspecified"))
    )
    (net (code "48") (name "unconnected-(SW5-D-Pad4)") (class "Default")
      (node (ref "SW5") (pin "4") (pinfunction "D_4") (pintype "unspecified"))
    )
    (net (code "49") (name "unconnected-(SW6-B-Pad2)") (class "Default")
      (node (ref "SW6") (pin "2") (pinfunction "B_2") (pintype "unspecified"))
    )
    (net (code "50") (name "unconnected-(SW6-D-Pad4)") (class "Default")
      (node (ref "SW6") (pin "4") (pinfunction "D_4") (pintype "unspecified"))
    )
    (net (code "51") (name "unconnected-(SW7-B-Pad2)") (class "Default")
      (node (ref "SW7") (pin "2") (pinfunction "B_2") (pintype "unspecified"))
    )
    (net (code "52") (name "unconnected-(SW7-D-Pad4)") (class "Default")
      (node (ref "SW7") (pin "4") (pinfunction "D_4") (pintype "unspecified"))
    )
    (net (code "53") (name "unconnected-(SW8-B-Pad2)") (class "Default")
      (node (ref "SW8") (pin "2") (pinfunction "B_2") (pintype "unspecified"))
    )
    (net (code "54") (name "unconnected-(SW8-D-Pad4)") (class "Default")
      (node (ref "SW8") (pin "4") (pinfunction "D_4") (pintype "unspecified"))
    )
    (net (code "55") (name "unconnected-(SW9-B-Pad2)") (class "Default")
      (node (ref "SW9") (pin "2") (pinfunction "B_2") (pintype "unspecified"))
    )
    (net (code "56") (name "unconnected-(SW9-D-Pad4)") (class "Default")
      (node (ref "SW9") (pin "4") (pinfunction "D_4") (pintype "unspecified"))
    )
    (net (code "57") (name "unconnected-(U1-CTS#-Pad9)") (class "Default")
      (node (ref "U1") (pin "9") (pinfunction "CTS#_9") (pintype "unspecified"))
    )
    (net (code "58") (name "unconnected-(U1-DCD#-Pad12)") (class "Default")
      (node (ref "U1") (pin "12") (pinfunction "DCD#_12") (pintype "unspecified"))
    )
    (net (code "59") (name "unconnected-(U1-DSR#-Pad10)") (class "Default")
      (node (ref "U1") (pin "10") (pinfunction "DSR#_10") (pintype "unspecified"))
    )
    (net (code "60") (name "unconnected-(U1-NC.-Pad7)") (class "Default")
      (node (ref "U1") (pin "7") (pinfunction "NC._7") (pintype "unspecified"))
    )
    (net (code "61") (name "unconnected-(U1-OUT#-Pad8)") (class "Default")
      (node (ref "U1") (pin "8") (pinfunction "OUT#_8") (pintype "unspecified"))
    )
    (net (code "62") (name "unconnected-(U1-RI#-Pad11)") (class "Default")
      (node (ref "U1") (pin "11") (pinfunction "RI#_11") (pintype "unspecified"))
    )
    (net (code "63") (name "unconnected-(U2-VOUT-Pad4)") (class "Default")
      (node (ref "U2") (pin "4") (pinfunction "VOUT_4") (pintype "unspecified"))
    )
    (net (code "64") (name "unconnected-(U3-GND-Pad39)") (class "Default")
      (node (ref "U3") (pin "39") (pinfunction "GND_39") (pintype "unspecified"))
    )
    (net (code "65") (name "unconnected-(U3-IO2-Pad24)") (class "Default")
      (node (ref "U3") (pin "24") (pinfunction "IO2_24") (pintype "unspecified"))
    )
    (net (code "66") (name "unconnected-(U3-IO12-Pad14)") (class "Default")
      (node (ref "U3") (pin "14") (pinfunction "IO12_14") (pintype "unspecified"))
    )
    (net (code "67") (name "unconnected-(U3-IO13-Pad16)") (class "Default")
      (node (ref "U3") (pin "16") (pinfunction "IO13_16") (pintype "unspecified"))
    )
    (net (code "68") (name "unconnected-(U3-IO14-Pad13)") (class "Default")
      (node (ref "U3") (pin "13") (pinfunction "IO14_13") (pintype "unspecified"))
    )
    (net (code "69") (name "unconnected-(U3-IO26-Pad11)") (class "Default")
      (node (ref "U3") (pin "11") (pinfunction "IO26_11") (pintype "unspecified"))
    )
    (net (code "70") (name "unconnected-(U3-IO27-Pad12)") (class "Default")
      (node (ref "U3") (pin "12") (pinfunction "IO27_12") (pintype "unspecified"))
    )
    (net (code "71") (name "unconnected-(U3-IO33-Pad9)") (class "Default")
      (node (ref "U3") (pin "9") (pinfunction "IO33_9") (pintype "unspecified"))
    )
    (net (code "72") (name "unconnected-(U3-IO34-Pad6)") (class "Default")
      (node (ref "U3") (pin "6") (pinfunction "IO34_6") (pintype "unspecified"))
    )
    (net (code "73") (name "unconnected-(U3-IO35-Pad7)") (class "Default")
      (node (ref "U3") (pin "7") (pinfunction "IO35_7") (pintype "unspecified"))
    )
    (net (code "74") (name "unconnected-(U3-NC-Pad17)") (class "Default")
      (node (ref "U3") (pin "17") (pinfunction "NC_17") (pintype "unspecified"))
    )
    (net (code "75") (name "unconnected-(U3-NC-Pad18)") (class "Default")
      (node (ref "U3") (pin "18") (pinfunction "NC_18") (pintype "unspecified"))
    )
    (net (code "76") (name "unconnected-(U3-NC-Pad19)") (class "Default")
      (node (ref "U3") (pin "19") (pinfunction "NC_19") (pintype "unspecified"))
    )
    (net (code "77") (name "unconnected-(U3-NC-Pad20)") (class "Default")
      (node (ref "U3") (pin "20") (pinfunction "NC_20") (pintype "unspecified"))
    )
    (net (code "78") (name "unconnected-(U3-NC-Pad21)") (class "Default")
      (node (ref "U3") (pin "21") (pinfunction "NC_21") (pintype "unspecified"))
    )
    (net (code "79") (name "unconnected-(U3-NC-Pad22)") (class "Default")
      (node (ref "U3") (pin "22") (pinfunction "NC_22") (pintype "unspecified"))
    )
    (net (code "80") (name "unconnected-(U3-NC-Pad32)") (class "Default")
      (node (ref "U3") (pin "32") (pinfunction "NC_32") (pintype "unspecified"))
    )
    (net (code "81") (name "unconnected-(U3-SENSOR_VN-Pad5)") (class "Default")
      (node (ref "U3") (pin "5") (pinfunction "SENSOR_VN_5") (pintype "unspecified"))
    )
    (net (code "82") (name "unconnected-(U3-SENSOR_VP-Pad4)") (class "Default")
      (node (ref "U3") (pin "4") (pinfunction "SENSOR_VP_4") (pintype "unspecified"))
    )
    (net (code "83") (name "unconnected-(U5-NC-Pad2)") (class "Default")
      (node (ref "U5") (pin "2") (pinfunction "NC_2") (pintype "unspecified"))
    )
    (net (code "84") (name "unconnected-(USBC1-DN2-PadB7)") (class "Default")
      (node (ref "USBC1") (pin "B7") (pinfunction "DN2_B7") (pintype "unspecified"))
    )
    (net (code "85") (name "unconnected-(USBC1-DP2-PadB6)") (class "Default")
      (node (ref "USBC1") (pin "B6") (pinfunction "DP2_B6") (pintype "unspecified"))
    )
    (net (code "86") (name "unconnected-(USBC1-EH-Pad1)") (class "Default")
      (node (ref "USBC1") (pin "1") (pinfunction "EH_1") (pintype "unspecified"))
    )
    (net (code "87") (name "unconnected-(USBC1-EH-Pad2)") (class "Default")
      (node (ref "USBC1") (pin "2") (pinfunction "EH_2") (pintype "unspecified"))
    )
    (net (code "88") (name "unconnected-(USBC1-EH-Pad3)") (class "Default")
      (node (ref "USBC1") (pin "3") (pinfunction "EH_3") (pintype "unspecified"))
    )
    (net (code "89") (name "unconnected-(USBC1-EH-Pad4)") (class "Default")
      (node (ref "USBC1") (pin "4") (pinfunction "EH_4") (pintype "unspecified"))
    )
    (net (code "90") (name "unconnected-(USBC1-SBU1-PadA8)") (class "Default")
      (node (ref "USBC1") (pin "A8") (pinfunction "SBU1_A8") (pintype "unspecified"))
    )
    (net (code "91") (name "unconnected-(USBC1-SBU2-PadB8)") (class "Default")
      (node (ref "USBC1") (pin "B8") (pinfunction "SBU2_B8") (pintype "unspecified"))
    )
  )
)
